# lora_32_v6.net
KiCad netlist of a schematic drawn in EAGLE
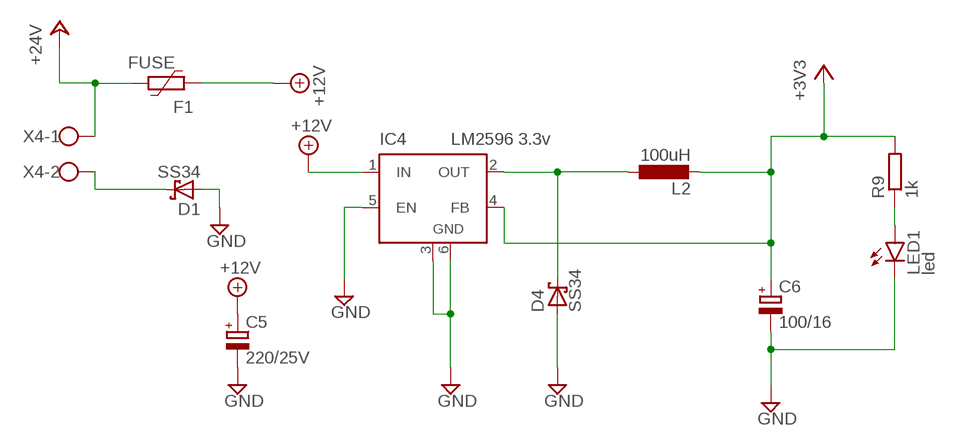
[diagram p0: schematic, sheet 1]
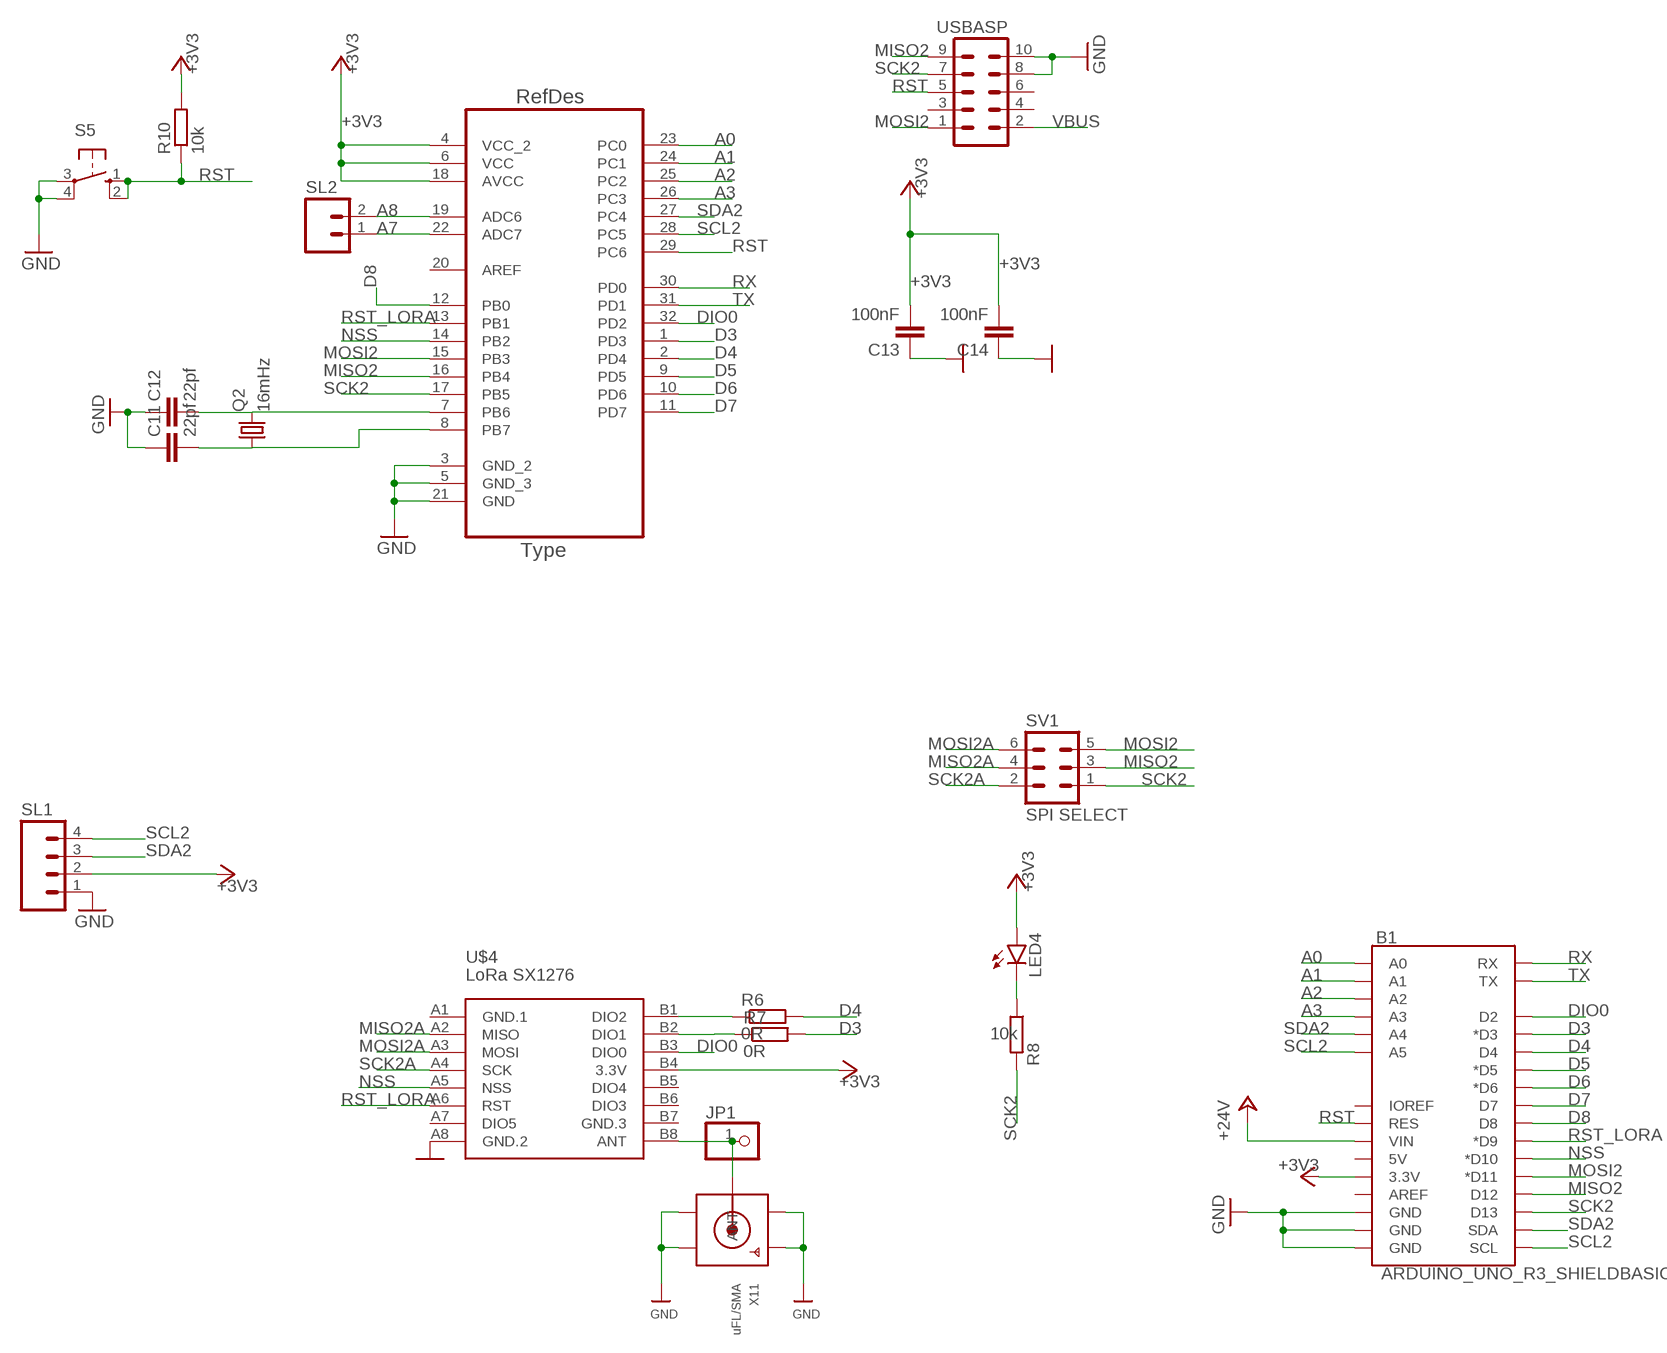
[diagram p1: schematic, sheet 2]
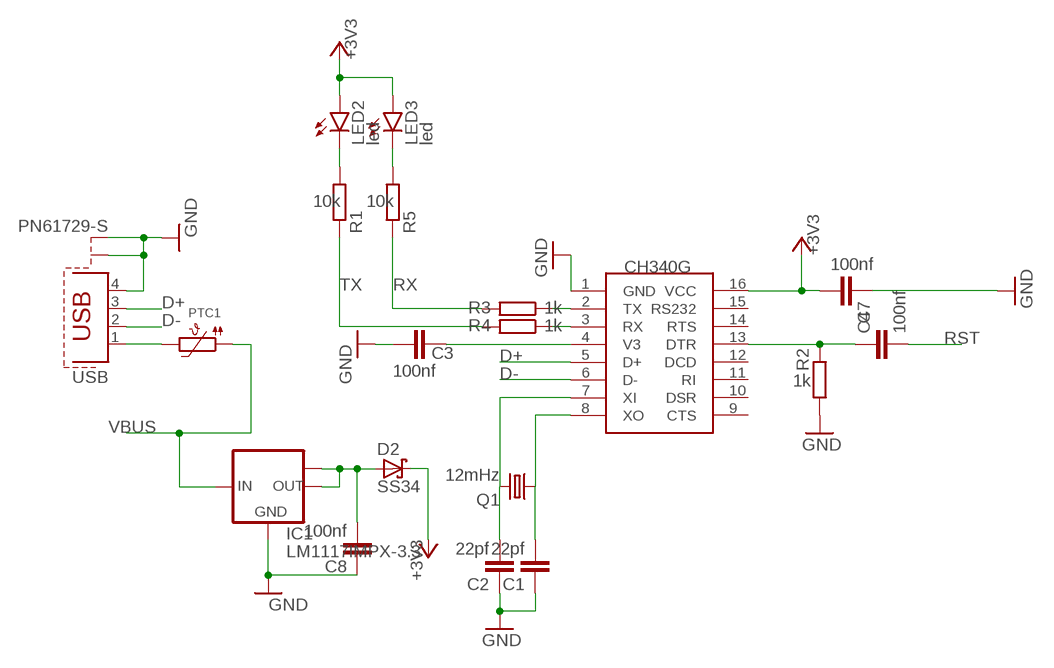
[diagram p2: schematic, sheet 3]

(export (version "E")
  (design (tool "Eeschema 10.0.6"))
  (components
    (comp (ref "B1")
      (value "ARDUINO_UNO_R3_SHIELDBASIC")
      (footprint "eagle-import:UNO_R3_SHIELD")
      (libsource (lib "eagle-import") (part "ARDUINO_UNO_R3_SHIELDBASIC"))
    )
    (comp (ref "C11")
      (value "22pf")
      (footprint "eagle-import:C0805K")
      (libsource (lib "eagle-import") (part "C-EUC0805K"))
    )
    (comp (ref "C12")
      (value "22pf")
      (footprint "eagle-import:C0805K")
      (libsource (lib "eagle-import") (part "C-EUC0805K"))
    )
    (comp (ref "C13")
      (value "100nF")
      (footprint "eagle-import:C0805K")
      (libsource (lib "eagle-import") (part "C-EUC0805K"))
    )
    (comp (ref "C14")
      (value "100nF")
      (footprint "eagle-import:C0805K")
      (libsource (lib "eagle-import") (part "C-EUC0805K"))
    )
    (comp (ref "JP1")
      (value "HEADER-1X1ROUND")
      (footprint "eagle-import:1X01_ROUND")
      (libsource (lib "eagle-import") (part "HEADER-1X1ROUND"))
    )
    (comp (ref "LED4")
      (value "LEDSML0805")
      (footprint "eagle-import:SML0805")
      (libsource (lib "eagle-import") (part "LEDSML0805"))
    )
    (comp (ref "Q2")
      (value "16mHz")
      (footprint "eagle-import:HC49UP")
      (libsource (lib "eagle-import") (part "CRYSTALHC49UP"))
    )
    (comp (ref "R6")
      (value "0R")
      (footprint "eagle-import:M0805")
      (libsource (lib "eagle-import") (part "R-EU_M0805"))
    )
    (comp (ref "R7")
      (value "0R")
      (footprint "eagle-import:M0805")
      (libsource (lib "eagle-import") (part "R-EU_M0805"))
    )
    (comp (ref "R8")
      (value "10k")
      (footprint "eagle-import:M0805")
      (libsource (lib "eagle-import") (part "R-EU_M0805"))
    )
    (comp (ref "R10")
      (value "10k")
      (footprint "eagle-import:M0805")
      (libsource (lib "eagle-import") (part "R-EU_M0805"))
    )
    (comp (ref "S5")
      (value "10-XX")
      (footprint "eagle-import:B3F-10XX")
      (fields (field (name "MPN") "B3F-1000"))
      (libsource (lib "eagle-import") (part "10-XX"))
    )
    (comp (ref "SL1")
      (value "M04")
      (footprint "eagle-import:04P")
      (libsource (lib "eagle-import") (part "M04"))
    )
    (comp (ref "SL2")
      (value "M02")
      (footprint "eagle-import:02P")
      (libsource (lib "eagle-import") (part "M02"))
    )
    (comp (ref "SV1")
      (value "SPI SELECT")
      (footprint "eagle-import:MA03-2")
      (libsource (lib "eagle-import") (part "MA03-2"))
    )
    (comp (ref "U$4")
      (value "LoRa SX1276")
      (footprint "eagle-import:WIRELESS-LORA-RFM95W#SMD")
      (libsource (lib "eagle-import") (part "WIRELESS-LORA-RFM95W#SMD"))
    )
    (comp (ref "U1")
      (value "ATMEGA328P-AU")
      (footprint "eagle-import:QFP80P900X900X120-32N")
      (libsource (lib "eagle-import") (part "ATMEGA328P-AU"))
    )
    (comp (ref "USBASP")
      (value "MA05-2")
      (footprint "eagle-import:MA05-2")
      (libsource (lib "eagle-import") (part "MA05-2"))
    )
    (comp (ref "X11")
      (value "uFL/SMA")
      (footprint "eagle-import:SMA_EDGELAUNCH_UFL")
      (libsource (lib "eagle-import") (part "SMACONNECTOR_EDGE_UFL"))
    )
    (comp (ref "C1")
      (value "22pf")
      (footprint "eagle-import:C0805K")
      (libsource (lib "eagle-import") (part "C-EUC0805K"))
    )
    (comp (ref "C2")
      (value "22pf")
      (footprint "eagle-import:C0805K")
      (libsource (lib "eagle-import") (part "C-EUC0805K"))
    )
    (comp (ref "C3")
      (value "100nf")
      (footprint "eagle-import:C0805K")
      (libsource (lib "eagle-import") (part "C-EUC0805K"))
    )
    (comp (ref "C4")
      (value "100nf")
      (footprint "eagle-import:C0805K")
      (libsource (lib "eagle-import") (part "C-EUC0805K"))
    )
    (comp (ref "C7")
      (value "100nf")
      (footprint "eagle-import:C0805K")
      (libsource (lib "eagle-import") (part "C-EUC0805K"))
    )
    (comp (ref "C8")
      (value "100nf")
      (footprint "eagle-import:C0805K")
      (libsource (lib "eagle-import") (part "C-EUC0805K"))
    )
    (comp (ref "D2")
      (value "SS34")
      (footprint "eagle-import:SMB")
      (libsource (lib "eagle-import") (part "SCHOTTKY-DIODESMD"))
    )
    (comp (ref "IC1")
      (value "LM1117IMPX-3.3")
      (footprint "eagle-import:SOT223")
      (libsource (lib "eagle-import") (part "LM1117IMPX-3.3"))
    )
    (comp (ref "LED2")
      (value "led")
      (footprint "eagle-import:SML0805")
      (libsource (lib "eagle-import") (part "LEDSML0805"))
    )
    (comp (ref "LED3")
      (value "led")
      (footprint "eagle-import:SML0805")
      (libsource (lib "eagle-import") (part "LEDSML0805"))
    )
    (comp (ref "PTC1")
      (value "PTC1206")
      (footprint "eagle-import:1206")
      (libsource (lib "eagle-import") (part "PTC1206"))
    )
    (comp (ref "Q1")
      (value "12mHz")
      (footprint "eagle-import:HC49UP")
      (libsource (lib "eagle-import") (part "CRYSTALHC49UP"))
    )
    (comp (ref "R1")
      (value "10k")
      (footprint "eagle-import:M0805")
      (libsource (lib "eagle-import") (part "R-EU_M0805"))
    )
    (comp (ref "R2")
      (value "1k")
      (footprint "eagle-import:M0805")
      (libsource (lib "eagle-import") (part "R-EU_M0805"))
    )
    (comp (ref "R3")
      (value "1k")
      (footprint "eagle-import:M0805")
      (libsource (lib "eagle-import") (part "R-EU_M0805"))
    )
    (comp (ref "R4")
      (value "1k")
      (footprint "eagle-import:M0805")
      (libsource (lib "eagle-import") (part "R-EU_M0805"))
    )
    (comp (ref "R5")
      (value "10k")
      (footprint "eagle-import:M0805")
      (libsource (lib "eagle-import") (part "R-EU_M0805"))
    )
    (comp (ref "U$5")
      (value "CH340G")
      (footprint "eagle-import:SOIC16")
      (libsource (lib "eagle-import") (part "CH340G"))
    )
    (comp (ref "USB")
      (value "PN61729-S")
      (footprint "eagle-import:PN61729-S")
      (libsource (lib "eagle-import") (part "PN61729-S"))
    )
    (comp (ref "C5")
      (value "220/25V")
      (footprint "eagle-import:PANASONIC_G")
      (libsource (lib "eagle-import") (part "CPOL-EUG"))
    )
    (comp (ref "C6")
      (value "100/16")
      (footprint "eagle-import:140CLH-0810")
      (libsource (lib "eagle-import") (part "CPOL-EU140CLH-0810"))
    )
    (comp (ref "D1")
      (value "SS34")
      (footprint "eagle-import:SMB")
      (libsource (lib "eagle-import") (part "SCHOTTKY-DIODESMD"))
    )
    (comp (ref "D4")
      (value "SS34")
      (footprint "eagle-import:SMB")
      (libsource (lib "eagle-import") (part "SCHOTTKY-DIODESMD"))
    )
    (comp (ref "F1")
      (value "FUSE")
      (footprint "eagle-import:1812L")
      (fields (field (name "MF") "Littelfuse") (field (name "MPN") "1812L010"))
      (libsource (lib "eagle-import") (part "?1812L010"))
    )
    (comp (ref "IC4")
      (value "LM2596 3.3v")
      (footprint "eagle-import:TO263-5")
      (libsource (lib "eagle-import") (part "LM2596S"))
    )
    (comp (ref "L2")
      (value "100uH")
      (footprint "eagle-import:6000-XXXX-RC")
      (libsource (lib "eagle-import") (part "L-EU6000-XXX-RC"))
    )
    (comp (ref "LED1")
      (value "led")
      (footprint "eagle-import:SML0805")
      (libsource (lib "eagle-import") (part "LEDSML0805"))
    )
    (comp (ref "R9")
      (value "1k")
      (footprint "eagle-import:M0805")
      (libsource (lib "eagle-import") (part "R-EU_M0805"))
    )
    (comp (ref "X4")
      (value "W237-102")
      (footprint "eagle-import:W237-102")
      (fields (field (name "MPN") "237-102"))
      (libsource (lib "eagle-import") (part "W237-102"))
    )
  )
  (nets
    (net (code "1") (name "+3V3") (class "Default")
      (node (ref "B1") (pin "3.3V") (pinfunction "3.3V_3.3V") (pintype "bidirectional"))
      (node (ref "C13") (pin "2") (pinfunction "2_2") (pintype "passive"))
      (node (ref "C14") (pin "2") (pinfunction "2_2") (pintype "passive"))
      (node (ref "C6") (pin "+") (pinfunction "+_+") (pintype "passive"))
      (node (ref "C7") (pin "2") (pinfunction "2_2") (pintype "passive"))
      (node (ref "D2") (pin "C") (pinfunction "C_C") (pintype "passive"))
      (node (ref "IC4") (pin "4") (pinfunction "FB_4") (pintype "input"))
      (node (ref "L2") (pin "2") (pinfunction "2_2") (pintype "passive"))
      (node (ref "LED2") (pin "A") (pinfunction "A_A") (pintype "passive"))
      (node (ref "LED3") (pin "A") (pinfunction "A_A") (pintype "passive"))
      (node (ref "LED4") (pin "A") (pinfunction "A_A") (pintype "passive"))
      (node (ref "R10") (pin "2") (pinfunction "2_2") (pintype "passive"))
      (node (ref "R9") (pin "2") (pinfunction "2_2") (pintype "passive"))
      (node (ref "SL1") (pin "2") (pinfunction "2_2") (pintype "passive"))
      (node (ref "U$4") (pin "B4") (pinfunction "3.3V_B4") (pintype "power_in"))
      (node (ref "U$5") (pin "16") (pinfunction "VCC_16") (pintype "bidirectional"))
      (node (ref "U1") (pin "18") (pinfunction "AVCC_18") (pintype "power_in"))
      (node (ref "U1") (pin "4") (pinfunction "VCC_2_4") (pintype "power_in"))
      (node (ref "U1") (pin "6") (pinfunction "VCC_6") (pintype "power_in"))
    )
    (net (code "2") (name "+12V") (class "Default")
      (node (ref "C5") (pin "+") (pinfunction "+_+") (pintype "passive"))
      (node (ref "F1") (pin "2") (pinfunction "2_2") (pintype "passive"))
      (node (ref "IC4") (pin "1") (pinfunction "IN_1") (pintype "input"))
    )
    (net (code "3") (name "+24V") (class "Default")
      (node (ref "B1") (pin "VIN") (pinfunction "VIN_VIN") (pintype "bidirectional"))
      (node (ref "F1") (pin "1") (pinfunction "1_1") (pintype "passive"))
      (node (ref "X4") (pin "1") (pinfunction "KL_1") (pintype "passive"))
    )
    (net (code "4") (name "A0") (class "Default")
      (node (ref "B1") (pin "A0") (pinfunction "A0_A0") (pintype "bidirectional"))
      (node (ref "U1") (pin "23") (pinfunction "PC0_23") (pintype "bidirectional"))
    )
    (net (code "5") (name "A1") (class "Default")
      (node (ref "B1") (pin "A1") (pinfunction "A1_A1") (pintype "bidirectional"))
      (node (ref "U1") (pin "24") (pinfunction "PC1_24") (pintype "bidirectional"))
    )
    (net (code "6") (name "A2") (class "Default")
      (node (ref "B1") (pin "A2") (pinfunction "A2_A2") (pintype "bidirectional"))
      (node (ref "U1") (pin "25") (pinfunction "PC2_25") (pintype "bidirectional"))
    )
    (net (code "7") (name "A3") (class "Default")
      (node (ref "B1") (pin "A3") (pinfunction "A3_A3") (pintype "bidirectional"))
      (node (ref "U1") (pin "26") (pinfunction "PC3_26") (pintype "bidirectional"))
    )
    (net (code "8") (name "A7") (class "Default")
      (node (ref "SL2") (pin "1") (pinfunction "1_1") (pintype "passive"))
      (node (ref "U1") (pin "22") (pinfunction "ADC7_22") (pintype "input"))
    )
    (net (code "9") (name "A8") (class "Default")
      (node (ref "SL2") (pin "2") (pinfunction "2_2") (pintype "passive"))
      (node (ref "U1") (pin "19") (pinfunction "ADC6_19") (pintype "input"))
    )
    (net (code "10") (name "D+") (class "Default")
      (node (ref "U$5") (pin "5") (pinfunction "D+_5") (pintype "bidirectional"))
      (node (ref "USB") (pin "3") (pinfunction "3_3") (pintype "passive"))
    )
    (net (code "11") (name "D-") (class "Default")
      (node (ref "U$5") (pin "6") (pinfunction "D-_6") (pintype "bidirectional"))
      (node (ref "USB") (pin "2") (pinfunction "2_2") (pintype "passive"))
    )
    (net (code "12") (name "D3") (class "Default")
      (node (ref "B1") (pin "D3") (pinfunction "*D3_D3") (pintype "bidirectional"))
      (node (ref "R7") (pin "2") (pinfunction "2_2") (pintype "passive"))
      (node (ref "U1") (pin "1") (pinfunction "PD3_1") (pintype "bidirectional"))
    )
    (net (code "13") (name "D4") (class "Default")
      (node (ref "B1") (pin "D4") (pinfunction "D4_D4") (pintype "bidirectional"))
      (node (ref "R6") (pin "2") (pinfunction "2_2") (pintype "passive"))
      (node (ref "U1") (pin "2") (pinfunction "PD4_2") (pintype "bidirectional"))
    )
    (net (code "14") (name "D5") (class "Default")
      (node (ref "B1") (pin "D5") (pinfunction "*D5_D5") (pintype "bidirectional"))
      (node (ref "U1") (pin "9") (pinfunction "PD5_9") (pintype "bidirectional"))
    )
    (net (code "15") (name "D6") (class "Default")
      (node (ref "B1") (pin "D6") (pinfunction "*D6_D6") (pintype "bidirectional"))
      (node (ref "U1") (pin "10") (pinfunction "PD6_10") (pintype "bidirectional"))
    )
    (net (code "16") (name "D7") (class "Default")
      (node (ref "B1") (pin "D7") (pinfunction "D7_D7") (pintype "bidirectional"))
      (node (ref "U1") (pin "11") (pinfunction "PD7_11") (pintype "bidirectional"))
    )
    (net (code "17") (name "D8") (class "Default")
      (node (ref "B1") (pin "D8") (pinfunction "D8_D8") (pintype "bidirectional"))
      (node (ref "U1") (pin "12") (pinfunction "PB0_12") (pintype "bidirectional"))
    )
    (net (code "18") (name "DIO0") (class "Default")
      (node (ref "B1") (pin "D2") (pinfunction "D2_D2") (pintype "bidirectional"))
      (node (ref "U$4") (pin "B3") (pinfunction "DIO0_B3") (pintype "bidirectional"))
      (node (ref "U1") (pin "32") (pinfunction "PD2_32") (pintype "bidirectional"))
    )
    (net (code "19") (name "GND") (class "Default")
      (node (ref "B1") (pin "GND@0") (pinfunction "GND_GND@0") (pintype "bidirectional"))
      (node (ref "B1") (pin "GND@1") (pinfunction "GND_GND@1") (pintype "bidirectional"))
      (node (ref "B1") (pin "GND@2") (pinfunction "GND_GND@2") (pintype "bidirectional"))
      (node (ref "C1") (pin "1") (pinfunction "1_1") (pintype "passive"))
      (node (ref "C11") (pin "1") (pinfunction "1_1") (pintype "passive"))
      (node (ref "C12") (pin "1") (pinfunction "1_1") (pintype "passive"))
      (node (ref "C13") (pin "1") (pinfunction "1_1") (pintype "passive"))
      (node (ref "C14") (pin "1") (pinfunction "1_1") (pintype "passive"))
      (node (ref "C2") (pin "1") (pinfunction "1_1") (pintype "passive"))
      (node (ref "C3") (pin "1") (pinfunction "1_1") (pintype "passive"))
      (node (ref "C5") (pin "-") (pinfunction "-_-") (pintype "passive"))
      (node (ref "C6") (pin "-") (pinfunction "-_-") (pintype "passive"))
      (node (ref "C7") (pin "1") (pinfunction "1_1") (pintype "passive"))
      (node (ref "C8") (pin "1") (pinfunction "1_1") (pintype "passive"))
      (node (ref "D1") (pin "A") (pinfunction "A_A") (pintype "passive"))
      (node (ref "D4") (pin "A") (pinfunction "A_A") (pintype "passive"))
      (node (ref "IC1") (pin "1") (pinfunction "GND_1") (pintype "input"))
      (node (ref "IC4") (pin "3") (pinfunction "GND_3") (pintype "power_in"))
      (node (ref "IC4") (pin "5") (pinfunction "EN_5") (pintype "input"))
      (node (ref "IC4") (pin "6") (pinfunction "GND_6") (pintype "power_in"))
      (node (ref "LED1") (pin "C") (pinfunction "C_C") (pintype "passive"))
      (node (ref "R2") (pin "1") (pinfunction "1_1") (pintype "passive"))
      (node (ref "S5") (pin "3") (pinfunction "P_3") (pintype "passive"))
      (node (ref "S5") (pin "4") (pinfunction "P1_4") (pintype "passive"))
      (node (ref "SL1") (pin "1") (pinfunction "1_1") (pintype "passive"))
      (node (ref "U$4") (pin "A8") (pinfunction "GND.2_A8") (pintype "power_in"))
      (node (ref "U$5") (pin "1") (pinfunction "GND_1") (pintype "bidirectional"))
      (node (ref "U1") (pin "21") (pinfunction "GND_21") (pintype "passive"))
      (node (ref "U1") (pin "3") (pinfunction "GND_2_3") (pintype "passive"))
      (node (ref "U1") (pin "5") (pinfunction "GND_3_5") (pintype "passive"))
      (node (ref "USB") (pin "4") (pinfunction "4_4") (pintype "passive"))
      (node (ref "USB") (pin "S1") (pinfunction "S1_S1") (pintype "passive"))
      (node (ref "USB") (pin "S2") (pinfunction "S2_S2") (pintype "passive"))
      (node (ref "USBASP") (pin "10") (pinfunction "10_10") (pintype "passive"))
      (node (ref "USBASP") (pin "8") (pinfunction "8_8") (pintype "passive"))
      (node (ref "X11") (pin "GND@1") (pinfunction "GND1_GND@1") (pintype "power_in"))
      (node (ref "X11") (pin "GND@2") (pinfunction "GND2_GND@2") (pintype "power_in"))
      (node (ref "X11") (pin "GND@3") (pinfunction "GND3_GND@3") (pintype "power_in"))
      (node (ref "X11") (pin "GND@4") (pinfunction "GND4_GND@4") (pintype "power_in"))
    )
    (net (code "20") (name "GND.1") (class "Default")
      (node (ref "U$4") (pin "A1") (pinfunction "GND.1_A1") (pintype "power_in"))
    )
    (net (code "21") (name "GND.3") (class "Default")
      (node (ref "U$4") (pin "B7") (pinfunction "GND.3_B7") (pintype "power_in"))
    )
    (net (code "22") (name "MISO2") (class "Default")
      (node (ref "B1") (pin "D12") (pinfunction "D12_D12") (pintype "bidirectional"))
      (node (ref "SV1") (pin "3") (pinfunction "3_3") (pintype "passive"))
      (node (ref "U1") (pin "16") (pinfunction "PB4_16") (pintype "bidirectional"))
      (node (ref "USBASP") (pin "9") (pinfunction "9_9") (pintype "passive"))
    )
    (net (code "23") (name "MISO2A") (class "Default")
      (node (ref "SV1") (pin "4") (pinfunction "4_4") (pintype "passive"))
      (node (ref "U$4") (pin "A2") (pinfunction "MISO_A2") (pintype "bidirectional"))
    )
    (net (code "24") (name "MOSI2") (class "Default")
      (node (ref "B1") (pin "D11") (pinfunction "*D11_D11") (pintype "bidirectional"))
      (node (ref "SV1") (pin "5") (pinfunction "5_5") (pintype "passive"))
      (node (ref "U1") (pin "15") (pinfunction "PB3_15") (pintype "bidirectional"))
      (node (ref "USBASP") (pin "1") (pinfunction "1_1") (pintype "passive"))
    )
    (net (code "25") (name "MOSI2A") (class "Default")
      (node (ref "SV1") (pin "6") (pinfunction "6_6") (pintype "passive"))
      (node (ref "U$4") (pin "A3") (pinfunction "MOSI_A3") (pintype "bidirectional"))
    )
    (net (code "26") (name "NSS") (class "Default")
      (node (ref "B1") (pin "D10") (pinfunction "*D10_D10") (pintype "bidirectional"))
      (node (ref "U$4") (pin "A5") (pinfunction "NSS_A5") (pintype "bidirectional"))
      (node (ref "U1") (pin "14") (pinfunction "PB2_14") (pintype "bidirectional"))
    )
    (net (code "27") (name "Net-(IC1-OUT)") (class "Default")
      (node (ref "C8") (pin "2") (pinfunction "2_2") (pintype "passive"))
      (node (ref "D2") (pin "A") (pinfunction "A_A") (pintype "passive"))
      (node (ref "IC1") (pin "2") (pinfunction "OUT_2") (pintype "passive"))
      (node (ref "IC1") (pin "TAB") (pinfunction "OUT1_TAB") (pintype "passive"))
    )
    (net (code "28") (name "Net-(IC4-OUT)") (class "Default")
      (node (ref "D4") (pin "C") (pinfunction "C_C") (pintype "passive"))
      (node (ref "IC4") (pin "2") (pinfunction "OUT_2") (pintype "output"))
      (node (ref "L2") (pin "1") (pinfunction "1_1") (pintype "passive"))
    )
    (net (code "29") (name "Net-(LED1-PadA)") (class "Default")
      (node (ref "LED1") (pin "A") (pinfunction "A_A") (pintype "passive"))
      (node (ref "R9") (pin "1") (pinfunction "1_1") (pintype "passive"))
    )
    (net (code "30") (name "Net-(LED2-PadC)") (class "Default")
      (node (ref "LED2") (pin "C") (pinfunction "C_C") (pintype "passive"))
      (node (ref "R1") (pin "1") (pinfunction "1_1") (pintype "passive"))
    )
    (net (code "31") (name "Net-(LED3-PadC)") (class "Default")
      (node (ref "LED3") (pin "C") (pinfunction "C_C") (pintype "passive"))
      (node (ref "R5") (pin "1") (pinfunction "1_1") (pintype "passive"))
    )
    (net (code "32") (name "Net-(LED4-PadC)") (class "Default")
      (node (ref "LED4") (pin "C") (pinfunction "C_C") (pintype "passive"))
      (node (ref "R8") (pin "1") (pinfunction "1_1") (pintype "passive"))
    )
    (net (code "33") (name "Net-(PTC1-Pad2)") (class "Default")
      (node (ref "PTC1") (pin "2") (pinfunction "2_2") (pintype "passive"))
      (node (ref "USB") (pin "1") (pinfunction "1_1") (pintype "passive"))
    )
    (net (code "34") (name "Net-(U$4-ANT)") (class "Default")
      (node (ref "JP1") (pin "1") (pinfunction "1_1") (pintype "passive"))
      (node (ref "U$4") (pin "B8") (pinfunction "ANT_B8") (pintype "passive"))
      (node (ref "X11") (pin "P") (pinfunction "ANT_P") (pintype "bidirectional"))
    )
    (net (code "35") (name "Net-(U$4-DIO1)") (class "Default")
      (node (ref "R7") (pin "1") (pinfunction "1_1") (pintype "passive"))
      (node (ref "U$4") (pin "B2") (pinfunction "DIO1_B2") (pintype "bidirectional"))
    )
    (net (code "36") (name "Net-(U$4-DIO2)") (class "Default")
      (node (ref "R6") (pin "1") (pinfunction "1_1") (pintype "passive"))
      (node (ref "U$4") (pin "B1") (pinfunction "DIO2_B1") (pintype "bidirectional"))
    )
    (net (code "37") (name "Net-(U$5-DTR)") (class "Default")
      (node (ref "C4") (pin "1") (pinfunction "1_1") (pintype "passive"))
      (node (ref "R2") (pin "2") (pinfunction "2_2") (pintype "passive"))
      (node (ref "U$5") (pin "13") (pinfunction "DTR_13") (pintype "bidirectional"))
    )
    (net (code "38") (name "Net-(U$5-RX)") (class "Default")
      (node (ref "R4") (pin "1") (pinfunction "1_1") (pintype "passive"))
      (node (ref "U$5") (pin "3") (pinfunction "RX_3") (pintype "bidirectional"))
    )
    (net (code "39") (name "Net-(U$5-TX)") (class "Default")
      (node (ref "R3") (pin "1") (pinfunction "1_1") (pintype "passive"))
      (node (ref "U$5") (pin "2") (pinfunction "TX_2") (pintype "bidirectional"))
    )
    (net (code "40") (name "Net-(U$5-V3)") (class "Default")
      (node (ref "C3") (pin "2") (pinfunction "2_2") (pintype "passive"))
      (node (ref "U$5") (pin "4") (pinfunction "V3_4") (pintype "bidirectional"))
    )
    (net (code "41") (name "Net-(U$5-XI)") (class "Default")
      (node (ref "C2") (pin "2") (pinfunction "2_2") (pintype "passive"))
      (node (ref "Q1") (pin "2") (pinfunction "2_2") (pintype "passive"))
      (node (ref "U$5") (pin "7") (pinfunction "XI_7") (pintype "bidirectional"))
    )
    (net (code "42") (name "Net-(U$5-XO)") (class "Default")
      (node (ref "C1") (pin "2") (pinfunction "2_2") (pintype "passive"))
      (node (ref "Q1") (pin "1") (pinfunction "1_1") (pintype "passive"))
      (node (ref "U$5") (pin "8") (pinfunction "XO_8") (pintype "bidirectional"))
    )
    (net (code "43") (name "Net-(U1-PB6)") (class "Default")
      (node (ref "C12") (pin "2") (pinfunction "2_2") (pintype "passive"))
      (node (ref "Q2") (pin "2") (pinfunction "2_2") (pintype "passive"))
      (node (ref "U1") (pin "7") (pinfunction "PB6_7") (pintype "bidirectional"))
    )
    (net (code "44") (name "Net-(U1-PB7)") (class "Default")
      (node (ref "C11") (pin "2") (pinfunction "2_2") (pintype "passive"))
      (node (ref "Q2") (pin "1") (pinfunction "1_1") (pintype "passive"))
      (node (ref "U1") (pin "8") (pinfunction "PB7_8") (pintype "bidirectional"))
    )
    (net (code "45") (name "Net-(X4B-KL)") (class "Default")
      (node (ref "D1") (pin "C") (pinfunction "C_C") (pintype "passive"))
      (node (ref "X4") (pin "2") (pinfunction "KL_2") (pintype "passive"))
    )
    (net (code "46") (name "RST") (class "Default")
      (node (ref "B1") (pin "RES") (pinfunction "RES_RES") (pintype "bidirectional"))
      (node (ref "C4") (pin "2") (pinfunction "2_2") (pintype "passive"))
      (node (ref "R10") (pin "1") (pinfunction "1_1") (pintype "passive"))
      (node (ref "S5") (pin "1") (pinfunction "S_1") (pintype "passive"))
      (node (ref "S5") (pin "2") (pinfunction "S1_2") (pintype "passive"))
      (node (ref "U1") (pin "29") (pinfunction "PC6_29") (pintype "bidirectional"))
      (node (ref "USBASP") (pin "5") (pinfunction "5_5") (pintype "passive"))
    )
    (net (code "47") (name "RST_LORA") (class "Default")
      (node (ref "B1") (pin "D9") (pinfunction "*D9_D9") (pintype "bidirectional"))
      (node (ref "U$4") (pin "A6") (pinfunction "RST_A6") (pintype "bidirectional"))
      (node (ref "U1") (pin "13") (pinfunction "PB1_13") (pintype "bidirectional"))
    )
    (net (code "48") (name "RX") (class "Default")
      (node (ref "B1") (pin "RX") (pinfunction "RX_RX") (pintype "bidirectional"))
      (node (ref "R3") (pin "2") (pinfunction "2_2") (pintype "passive"))
      (node (ref "R5") (pin "2") (pinfunction "2_2") (pintype "passive"))
      (node (ref "U1") (pin "30") (pinfunction "PD0_30") (pintype "bidirectional"))
    )
    (net (code "49") (name "SCK2") (class "Default")
      (node (ref "B1") (pin "D13") (pinfunction "D13_D13") (pintype "bidirectional"))
      (node (ref "R8") (pin "2") (pinfunction "2_2") (pintype "passive"))
      (node (ref "SV1") (pin "1") (pinfunction "1_1") (pintype "passive"))
      (node (ref "U1") (pin "17") (pinfunction "PB5_17") (pintype "bidirectional"))
      (node (ref "USBASP") (pin "7") (pinfunction "7_7") (pintype "passive"))
    )
    (net (code "50") (name "SCK2A") (class "Default")
      (node (ref "SV1") (pin "2") (pinfunction "2_2") (pintype "passive"))
      (node (ref "U$4") (pin "A4") (pinfunction "SCK_A4") (pintype "bidirectional"))
    )
    (net (code "51") (name "SCL2") (class "Default")
      (node (ref "B1") (pin "A5") (pinfunction "A5_A5") (pintype "bidirectional"))
      (node (ref "B1") (pin "SCL") (pinfunction "SCL_SCL") (pintype "bidirectional"))
      (node (ref "SL1") (pin "4") (pinfunction "4_4") (pintype "passive"))
      (node (ref "U1") (pin "28") (pinfunction "PC5_28") (pintype "bidirectional"))
    )
    (net (code "52") (name "SDA2") (class "Default")
      (node (ref "B1") (pin "A4") (pinfunction "A4_A4") (pintype "bidirectional"))
      (node (ref "B1") (pin "SDA") (pinfunction "SDA_SDA") (pintype "bidirectional"))
      (node (ref "SL1") (pin "3") (pinfunction "3_3") (pintype "passive"))
      (node (ref "U1") (pin "27") (pinfunction "PC4_27") (pintype "bidirectional"))
    )
    (net (code "53") (name "TX") (class "Default")
      (node (ref "B1") (pin "TX") (pinfunction "TX_TX") (pintype "bidirectional"))
      (node (ref "R1") (pin "2") (pinfunction "2_2") (pintype "passive"))
      (node (ref "R4") (pin "2") (pinfunction "2_2") (pintype "passive"))
      (node (ref "U1") (pin "31") (pinfunction "PD1_31") (pintype "bidirectional"))
    )
    (net (code "54") (name "VBUS") (class "Default")
      (node (ref "IC1") (pin "3") (pinfunction "IN_3") (pintype "input"))
      (node (ref "PTC1") (pin "1") (pinfunction "1_1") (pintype "passive"))
      (node (ref "USBASP") (pin "2") (pinfunction "2_2") (pintype "passive"))
    )
    (net (code "55") (name "unconnected-(B1-Pad5V)") (class "Default")
      (node (ref "B1") (pin "5V") (pinfunction "5V_5V") (pintype "bidirectional"))
    )
    (net (code "56") (name "unconnected-(B1-PadAREF)") (class "Default")
      (node (ref "B1") (pin "AREF") (pinfunction "AREF_AREF") (pintype "bidirectional"))
    )
    (net (code "57") (name "unconnected-(B1-PadIOREF)") (class "Default")
      (node (ref "B1") (pin "IOREF") (pinfunction "IOREF_IOREF") (pintype "bidirectional"))
    )
    (net (code "58") (name "unconnected-(U$4-DIO3-PadB6)") (class "Default")
      (node (ref "U$4") (pin "B6") (pinfunction "DIO3_B6") (pintype "bidirectional"))
    )
    (net (code "59") (name "unconnected-(U$4-DIO4-PadB5)") (class "Default")
      (node (ref "U$4") (pin "B5") (pinfunction "DIO4_B5") (pintype "bidirectional"))
    )
    (net (code "60") (name "unconnected-(U$4-DIO5-PadA7)") (class "Default")
      (node (ref "U$4") (pin "A7") (pinfunction "DIO5_A7") (pintype "bidirectional"))
    )
    (net (code "61") (name "unconnected-(U$5-CTS-Pad9)") (class "Default")
      (node (ref "U$5") (pin "9") (pinfunction "CTS_9") (pintype "bidirectional"))
    )
    (net (code "62") (name "unconnected-(U$5-DCD-Pad12)") (class "Default")
      (node (ref "U$5") (pin "12") (pinfunction "DCD_12") (pintype "bidirectional"))
    )
    (net (code "63") (name "unconnected-(U$5-DSR-Pad10)") (class "Default")
      (node (ref "U$5") (pin "10") (pinfunction "DSR_10") (pintype "bidirectional"))
    )
    (net (code "64") (name "unconnected-(U$5-RI-Pad11)") (class "Default")
      (node (ref "U$5") (pin "11") (pinfunction "RI_11") (pintype "bidirectional"))
    )
    (net (code "65") (name "unconnected-(U$5-RS232-Pad15)") (class "Default")
      (node (ref "U$5") (pin "15") (pinfunction "RS232_15") (pintype "bidirectional"))
    )
    (net (code "66") (name "unconnected-(U$5-RTS-Pad14)") (class "Default")
      (node (ref "U$5") (pin "14") (pinfunction "RTS_14") (pintype "bidirectional"))
    )
    (net (code "67") (name "unconnected-(U1-AREF-Pad20)") (class "Default")
      (node (ref "U1") (pin "20") (pinfunction "AREF_20") (pintype "input"))
    )
    (net (code "68") (name "unconnected-(USBASP-Pad3)") (class "Default")
      (node (ref "USBASP") (pin "3") (pinfunction "3_3") (pintype "passive"))
    )
    (net (code "69") (name "unconnected-(USBASP-Pad4)") (class "Default")
      (node (ref "USBASP") (pin "4") (pinfunction "4_4") (pintype "passive"))
    )
    (net (code "70") (name "unconnected-(USBASP-Pad6)") (class "Default")
      (node (ref "USBASP") (pin "6") (pinfunction "6_6") (pintype "passive"))
    )
  )
)
